# INTERFACE.net
KiCad netlist of a schematic drawn in Altium Designer
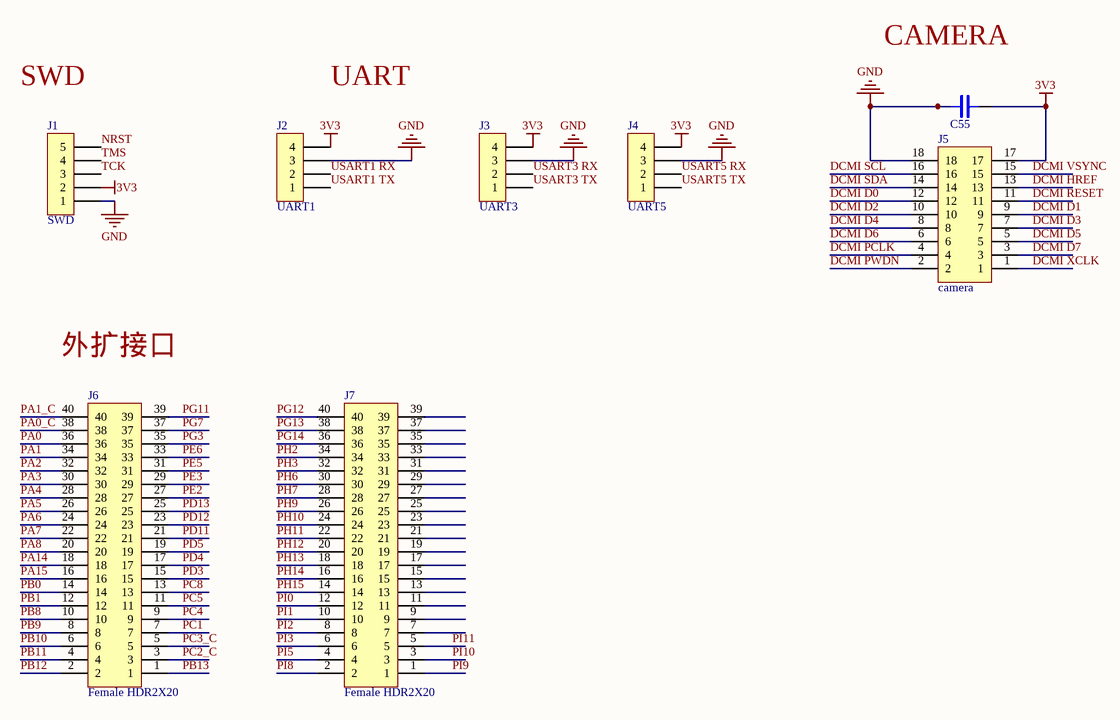
[diagram p0: INTERFACE.SchDoc]

(export (version "E")
  (design (tool "Eeschema 10.0.6"))
  (components
    (comp (ref "C55")
      (value "104")
      (footprint "CAP-1812")
      (description "Capacitor")
      (libsource (lib "General") (part "CAP"))
    )
    (comp (ref "J1") (value "SWD") (footprint "Pin HDR1X5/2mm-W") (libsource (lib "排针") (part "Pin HDR1X5")))
    (comp (ref "J2")
      (value "UART1")
      (footprint "Fe-HDR1X4/2.54-S")
      (libsource (lib "排母") (part "Female HDR1X4"))
    )
    (comp (ref "J3")
      (value "UART3")
      (footprint "Fe-HDR1X4/2.54-S")
      (libsource (lib "排母") (part "Female HDR1X4"))
    )
    (comp (ref "J4")
      (value "UART5")
      (footprint "Fe-HDR1X4/2.54-S")
      (libsource (lib "排母") (part "Female HDR1X4"))
    )
    (comp (ref "J5")
      (value "camera")
      (footprint "Fe-HDR2X9/2.54-S")
      (libsource (lib "排母") (part "Female HDR2X9"))
    )
    (comp (ref "J6")
      (value "Female HDR2X20")
      (footprint "Fe-HDR2X20/2.54-S")
      (libsource (lib "排母") (part "Female HDR2X20"))
    )
    (comp (ref "J7")
      (value "Female HDR2X20")
      (footprint "Fe-HDR2X20/2.54-S")
      (libsource (lib "排母") (part "Female HDR2X20"))
    )
  )
  (nets
    (net (code "1") (name "/DCMI D0") (class "Default")
      (node (ref "J5") (pin "12") (pinfunction "12_12") (pintype "passive"))
    )
    (net (code "2") (name "/DCMI D1") (class "Default")
      (node (ref "J5") (pin "9") (pinfunction "9_9") (pintype "passive"))
    )
    (net (code "3") (name "/DCMI D2") (class "Default")
      (node (ref "J5") (pin "10") (pinfunction "10_10") (pintype "passive"))
    )
    (net (code "4") (name "/DCMI D3") (class "Default")
      (node (ref "J5") (pin "7") (pinfunction "7_7") (pintype "passive"))
    )
    (net (code "5") (name "/DCMI D4") (class "Default")
      (node (ref "J5") (pin "8") (pinfunction "8_8") (pintype "passive"))
    )
    (net (code "6") (name "/DCMI D5") (class "Default")
      (node (ref "J5") (pin "5") (pinfunction "5_5") (pintype "passive"))
    )
    (net (code "7") (name "/DCMI D6") (class "Default")
      (node (ref "J5") (pin "6") (pinfunction "6_6") (pintype "passive"))
    )
    (net (code "8") (name "/DCMI D7") (class "Default")
      (node (ref "J5") (pin "3") (pinfunction "3_3") (pintype "passive"))
    )
    (net (code "9") (name "/DCMI HREF") (class "Default")
      (node (ref "J5") (pin "13") (pinfunction "13_13") (pintype "passive"))
    )
    (net (code "10") (name "/DCMI PCLK") (class "Default")
      (node (ref "J5") (pin "4") (pinfunction "4_4") (pintype "passive"))
    )
    (net (code "11") (name "/DCMI PWDN") (class "Default")
      (node (ref "J5") (pin "2") (pinfunction "2_2") (pintype "passive"))
    )
    (net (code "12") (name "/DCMI RESET") (class "Default")
      (node (ref "J5") (pin "11") (pinfunction "11_11") (pintype "passive"))
    )
    (net (code "13") (name "/DCMI SCL") (class "Default")
      (node (ref "J5") (pin "16") (pinfunction "16_16") (pintype "passive"))
    )
    (net (code "14") (name "/DCMI SDA") (class "Default")
      (node (ref "J5") (pin "14") (pinfunction "14_14") (pintype "passive"))
    )
    (net (code "15") (name "/DCMI VSYNC") (class "Default")
      (node (ref "J5") (pin "15") (pinfunction "15_15") (pintype "passive"))
    )
    (net (code "16") (name "/DCMI XCLK") (class "Default")
      (node (ref "J5") (pin "1") (pinfunction "1_1") (pintype "passive"))
    )
    (net (code "17") (name "/NRST") (class "Default")
      (node (ref "J1") (pin "5") (pinfunction "5_5") (pintype "passive"))
    )
    (net (code "18") (name "/PA0") (class "Default")
      (node (ref "J6") (pin "36") (pinfunction "36_36") (pintype "passive"))
    )
    (net (code "19") (name "/PA0_C") (class "Default")
      (node (ref "J6") (pin "38") (pinfunction "38_38") (pintype "passive"))
    )
    (net (code "20") (name "/PA1") (class "Default")
      (node (ref "J6") (pin "34") (pinfunction "34_34") (pintype "passive"))
    )
    (net (code "21") (name "/PA1_C") (class "Default")
      (node (ref "J6") (pin "40") (pinfunction "40_40") (pintype "passive"))
    )
    (net (code "22") (name "/PA2") (class "Default")
      (node (ref "J6") (pin "32") (pinfunction "32_32") (pintype "passive"))
    )
    (net (code "23") (name "/PA3") (class "Default")
      (node (ref "J6") (pin "30") (pinfunction "30_30") (pintype "passive"))
    )
    (net (code "24") (name "/PA4") (class "Default")
      (node (ref "J6") (pin "28") (pinfunction "28_28") (pintype "passive"))
    )
    (net (code "25") (name "/PA5") (class "Default")
      (node (ref "J6") (pin "26") (pinfunction "26_26") (pintype "passive"))
    )
    (net (code "26") (name "/PA6") (class "Default")
      (node (ref "J6") (pin "24") (pinfunction "24_24") (pintype "passive"))
    )
    (net (code "27") (name "/PA7") (class "Default")
      (node (ref "J6") (pin "22") (pinfunction "22_22") (pintype "passive"))
    )
    (net (code "28") (name "/PA8") (class "Default")
      (node (ref "J6") (pin "20") (pinfunction "20_20") (pintype "passive"))
    )
    (net (code "29") (name "/PA14") (class "Default")
      (node (ref "J6") (pin "18") (pinfunction "18_18") (pintype "passive"))
    )
    (net (code "30") (name "/PA15") (class "Default")
      (node (ref "J6") (pin "16") (pinfunction "16_16") (pintype "passive"))
    )
    (net (code "31") (name "/PB0") (class "Default")
      (node (ref "J6") (pin "14") (pinfunction "14_14") (pintype "passive"))
    )
    (net (code "32") (name "/PB1") (class "Default")
      (node (ref "J6") (pin "12") (pinfunction "12_12") (pintype "passive"))
    )
    (net (code "33") (name "/PB8") (class "Default")
      (node (ref "J6") (pin "10") (pinfunction "10_10") (pintype "passive"))
    )
    (net (code "34") (name "/PB9") (class "Default")
      (node (ref "J6") (pin "8") (pinfunction "8_8") (pintype "passive"))
    )
    (net (code "35") (name "/PB10") (class "Default")
      (node (ref "J6") (pin "6") (pinfunction "6_6") (pintype "passive"))
    )
    (net (code "36") (name "/PB11") (class "Default")
      (node (ref "J6") (pin "4") (pinfunction "4_4") (pintype "passive"))
    )
    (net (code "37") (name "/PB12") (class "Default")
      (node (ref "J6") (pin "2") (pinfunction "2_2") (pintype "passive"))
    )
    (net (code "38") (name "/PB13") (class "Default")
      (node (ref "J6") (pin "1") (pinfunction "1_1") (pintype "passive"))
    )
    (net (code "39") (name "/PC1") (class "Default")
      (node (ref "J6") (pin "7") (pinfunction "7_7") (pintype "passive"))
    )
    (net (code "40") (name "/PC2_C") (class "Default")
      (node (ref "J6") (pin "3") (pinfunction "3_3") (pintype "passive"))
    )
    (net (code "41") (name "/PC3_C") (class "Default")
      (node (ref "J6") (pin "5") (pinfunction "5_5") (pintype "passive"))
    )
    (net (code "42") (name "/PC4") (class "Default")
      (node (ref "J6") (pin "9") (pinfunction "9_9") (pintype "passive"))
    )
    (net (code "43") (name "/PC5") (class "Default")
      (node (ref "J6") (pin "11") (pinfunction "11_11") (pintype "passive"))
    )
    (net (code "44") (name "/PC8") (class "Default")
      (node (ref "J6") (pin "13") (pinfunction "13_13") (pintype "passive"))
    )
    (net (code "45") (name "/PD3") (class "Default")
      (node (ref "J6") (pin "15") (pinfunction "15_15") (pintype "passive"))
    )
    (net (code "46") (name "/PD4") (class "Default")
      (node (ref "J6") (pin "17") (pinfunction "17_17") (pintype "passive"))
    )
    (net (code "47") (name "/PD5") (class "Default")
      (node (ref "J6") (pin "19") (pinfunction "19_19") (pintype "passive"))
    )
    (net (code "48") (name "/PD11") (class "Default")
      (node (ref "J6") (pin "21") (pinfunction "21_21") (pintype "passive"))
    )
    (net (code "49") (name "/PD12") (class "Default")
      (node (ref "J6") (pin "23") (pinfunction "23_23") (pintype "passive"))
    )
    (net (code "50") (name "/PD13") (class "Default")
      (node (ref "J6") (pin "25") (pinfunction "25_25") (pintype "passive"))
    )
    (net (code "51") (name "/PE2") (class "Default")
      (node (ref "J6") (pin "27") (pinfunction "27_27") (pintype "passive"))
    )
    (net (code "52") (name "/PE3") (class "Default")
      (node (ref "J6") (pin "29") (pinfunction "29_29") (pintype "passive"))
    )
    (net (code "53") (name "/PE5") (class "Default")
      (node (ref "J6") (pin "31") (pinfunction "31_31") (pintype "passive"))
    )
    (net (code "54") (name "/PE6") (class "Default")
      (node (ref "J6") (pin "33") (pinfunction "33_33") (pintype "passive"))
    )
    (net (code "55") (name "/PG3") (class "Default")
      (node (ref "J6") (pin "35") (pinfunction "35_35") (pintype "passive"))
    )
    (net (code "56") (name "/PG7") (class "Default")
      (node (ref "J6") (pin "37") (pinfunction "37_37") (pintype "passive"))
    )
    (net (code "57") (name "/PG11") (class "Default")
      (node (ref "J6") (pin "39") (pinfunction "39_39") (pintype "passive"))
    )
    (net (code "58") (name "/PG12") (class "Default")
      (node (ref "J7") (pin "40") (pinfunction "40_40") (pintype "passive"))
    )
    (net (code "59") (name "/PG13") (class "Default")
      (node (ref "J7") (pin "38") (pinfunction "38_38") (pintype "passive"))
    )
    (net (code "60") (name "/PG14") (class "Default")
      (node (ref "J7") (pin "36") (pinfunction "36_36") (pintype "passive"))
    )
    (net (code "61") (name "/PH2") (class "Default")
      (node (ref "J7") (pin "34") (pinfunction "34_34") (pintype "passive"))
    )
    (net (code "62") (name "/PH3") (class "Default")
      (node (ref "J7") (pin "32") (pinfunction "32_32") (pintype "passive"))
    )
    (net (code "63") (name "/PH6") (class "Default")
      (node (ref "J7") (pin "30") (pinfunction "30_30") (pintype "passive"))
    )
    (net (code "64") (name "/PH7") (class "Default")
      (node (ref "J7") (pin "28") (pinfunction "28_28") (pintype "passive"))
    )
    (net (code "65") (name "/PH9") (class "Default")
      (node (ref "J7") (pin "26") (pinfunction "26_26") (pintype "passive"))
    )
    (net (code "66") (name "/PH10") (class "Default")
      (node (ref "J7") (pin "24") (pinfunction "24_24") (pintype "passive"))
    )
    (net (code "67") (name "/PH11") (class "Default")
      (node (ref "J7") (pin "22") (pinfunction "22_22") (pintype "passive"))
    )
    (net (code "68") (name "/PH12") (class "Default")
      (node (ref "J7") (pin "20") (pinfunction "20_20") (pintype "passive"))
    )
    (net (code "69") (name "/PH13") (class "Default")
      (node (ref "J7") (pin "18") (pinfunction "18_18") (pintype "passive"))
    )
    (net (code "70") (name "/PH14") (class "Default")
      (node (ref "J7") (pin "16") (pinfunction "16_16") (pintype "passive"))
    )
    (net (code "71") (name "/PH15") (class "Default")
      (node (ref "J7") (pin "14") (pinfunction "14_14") (pintype "passive"))
    )
    (net (code "72") (name "/PI0") (class "Default")
      (node (ref "J7") (pin "12") (pinfunction "12_12") (pintype "passive"))
    )
    (net (code "73") (name "/PI1") (class "Default")
      (node (ref "J7") (pin "10") (pinfunction "10_10") (pintype "passive"))
    )
    (net (code "74") (name "/PI2") (class "Default")
      (node (ref "J7") (pin "8") (pinfunction "8_8") (pintype "passive"))
    )
    (net (code "75") (name "/PI3") (class "Default")
      (node (ref "J7") (pin "6") (pinfunction "6_6") (pintype "passive"))
    )
    (net (code "76") (name "/PI5") (class "Default")
      (node (ref "J7") (pin "4") (pinfunction "4_4") (pintype "passive"))
    )
    (net (code "77") (name "/PI8") (class "Default")
      (node (ref "J7") (pin "2") (pinfunction "2_2") (pintype "passive"))
    )
    (net (code "78") (name "/PI9") (class "Default")
      (node (ref "J7") (pin "1") (pinfunction "1_1") (pintype "passive"))
    )
    (net (code "79") (name "/PI10") (class "Default")
      (node (ref "J7") (pin "3") (pinfunction "3_3") (pintype "passive"))
    )
    (net (code "80") (name "/PI11") (class "Default")
      (node (ref "J7") (pin "5") (pinfunction "5_5") (pintype "passive"))
    )
    (net (code "81") (name "/TCK") (class "Default")
      (node (ref "J1") (pin "3") (pinfunction "3_3") (pintype "passive"))
    )
    (net (code "82") (name "/TMS") (class "Default")
      (node (ref "J1") (pin "4") (pinfunction "4_4") (pintype "passive"))
    )
    (net (code "83") (name "/USART1 RX") (class "Default")
      (node (ref "J2") (pin "2") (pinfunction "2_2") (pintype "passive"))
    )
    (net (code "84") (name "/USART1 TX") (class "Default")
      (node (ref "J2") (pin "1") (pinfunction "1_1") (pintype "passive"))
    )
    (net (code "85") (name "/USART3 RX") (class "Default")
      (node (ref "J3") (pin "2") (pinfunction "2_2") (pintype "passive"))
    )
    (net (code "86") (name "/USART3 TX") (class "Default")
      (node (ref "J3") (pin "1") (pinfunction "1_1") (pintype "passive"))
    )
    (net (code "87") (name "/USART5 RX") (class "Default")
      (node (ref "J4") (pin "2") (pinfunction "2_2") (pintype "passive"))
    )
    (net (code "88") (name "/USART5 TX") (class "Default")
      (node (ref "J4") (pin "1") (pinfunction "1_1") (pintype "passive"))
    )
    (net (code "89") (name "3V3") (class "Default")
      (node (ref "C55") (pin "1") (pinfunction "1_1") (pintype "passive"))
      (node (ref "J1") (pin "2") (pinfunction "2_2") (pintype "passive"))
      (node (ref "J2") (pin "4") (pinfunction "4_4") (pintype "passive"))
      (node (ref "J3") (pin "4") (pinfunction "4_4") (pintype "passive"))
      (node (ref "J4") (pin "4") (pinfunction "4_4") (pintype "passive"))
      (node (ref "J5") (pin "17") (pinfunction "17_17") (pintype "passive"))
    )
    (net (code "90") (name "GND") (class "Default")
      (node (ref "C55") (pin "2") (pinfunction "2_2") (pintype "passive"))
      (node (ref "J1") (pin "1") (pinfunction "1_1") (pintype "passive"))
      (node (ref "J2") (pin "3") (pinfunction "3_3") (pintype "passive"))
      (node (ref "J3") (pin "3") (pinfunction "3_3") (pintype "passive"))
      (node (ref "J4") (pin "3") (pinfunction "3_3") (pintype "passive"))
      (node (ref "J5") (pin "18") (pinfunction "18_18") (pintype "passive"))
    )
    (net (code "91") (name "unconnected-(J7-Pad7)") (class "Default")
      (node (ref "J7") (pin "7") (pinfunction "7_7") (pintype "passive"))
    )
    (net (code "92") (name "unconnected-(J7-Pad9)") (class "Default")
      (node (ref "J7") (pin "9") (pinfunction "9_9") (pintype "passive"))
    )
    (net (code "93") (name "unconnected-(J7-Pad11)") (class "Default")
      (node (ref "J7") (pin "11") (pinfunction "11_11") (pintype "passive"))
    )
    (net (code "94") (name "unconnected-(J7-Pad13)") (class "Default")
      (node (ref "J7") (pin "13") (pinfunction "13_13") (pintype "passive"))
    )
    (net (code "95") (name "unconnected-(J7-Pad15)") (class "Default")
      (node (ref "J7") (pin "15") (pinfunction "15_15") (pintype "passive"))
    )
    (net (code "96") (name "unconnected-(J7-Pad17)") (class "Default")
      (node (ref "J7") (pin "17") (pinfunction "17_17") (pintype "passive"))
    )
    (net (code "97") (name "unconnected-(J7-Pad19)") (class "Default")
      (node (ref "J7") (pin "19") (pinfunction "19_19") (pintype "passive"))
    )
    (net (code "98") (name "unconnected-(J7-Pad21)") (class "Default")
      (node (ref "J7") (pin "21") (pinfunction "21_21") (pintype "passive"))
    )
    (net (code "99") (name "unconnected-(J7-Pad23)") (class "Default")
      (node (ref "J7") (pin "23") (pinfunction "23_23") (pintype "passive"))
    )
    (net (code "100") (name "unconnected-(J7-Pad25)") (class "Default")
      (node (ref "J7") (pin "25") (pinfunction "25_25") (pintype "passive"))
    )
    (net (code "101") (name "unconnected-(J7-Pad27)") (class "Default")
      (node (ref "J7") (pin "27") (pinfunction "27_27") (pintype "passive"))
    )
    (net (code "102") (name "unconnected-(J7-Pad29)") (class "Default")
      (node (ref "J7") (pin "29") (pinfunction "29_29") (pintype "passive"))
    )
    (net (code "103") (name "unconnected-(J7-Pad31)") (class "Default")
      (node (ref "J7") (pin "31") (pinfunction "31_31") (pintype "passive"))
    )
    (net (code "104") (name "unconnected-(J7-Pad33)") (class "Default")
      (node (ref "J7") (pin "33") (pinfunction "33_33") (pintype "passive"))
    )
    (net (code "105") (name "unconnected-(J7-Pad35)") (class "Default")
      (node (ref "J7") (pin "35") (pinfunction "35_35") (pintype "passive"))
    )
    (net (code "106") (name "unconnected-(J7-Pad37)") (class "Default")
      (node (ref "J7") (pin "37") (pinfunction "37_37") (pintype "passive"))
    )
    (net (code "107") (name "unconnected-(J7-Pad39)") (class "Default")
      (node (ref "J7") (pin "39") (pinfunction "39_39") (pintype "passive"))
    )
  )
)
